# Vale_Project_02.net
KiCad netlist of a schematic drawn in EAGLE
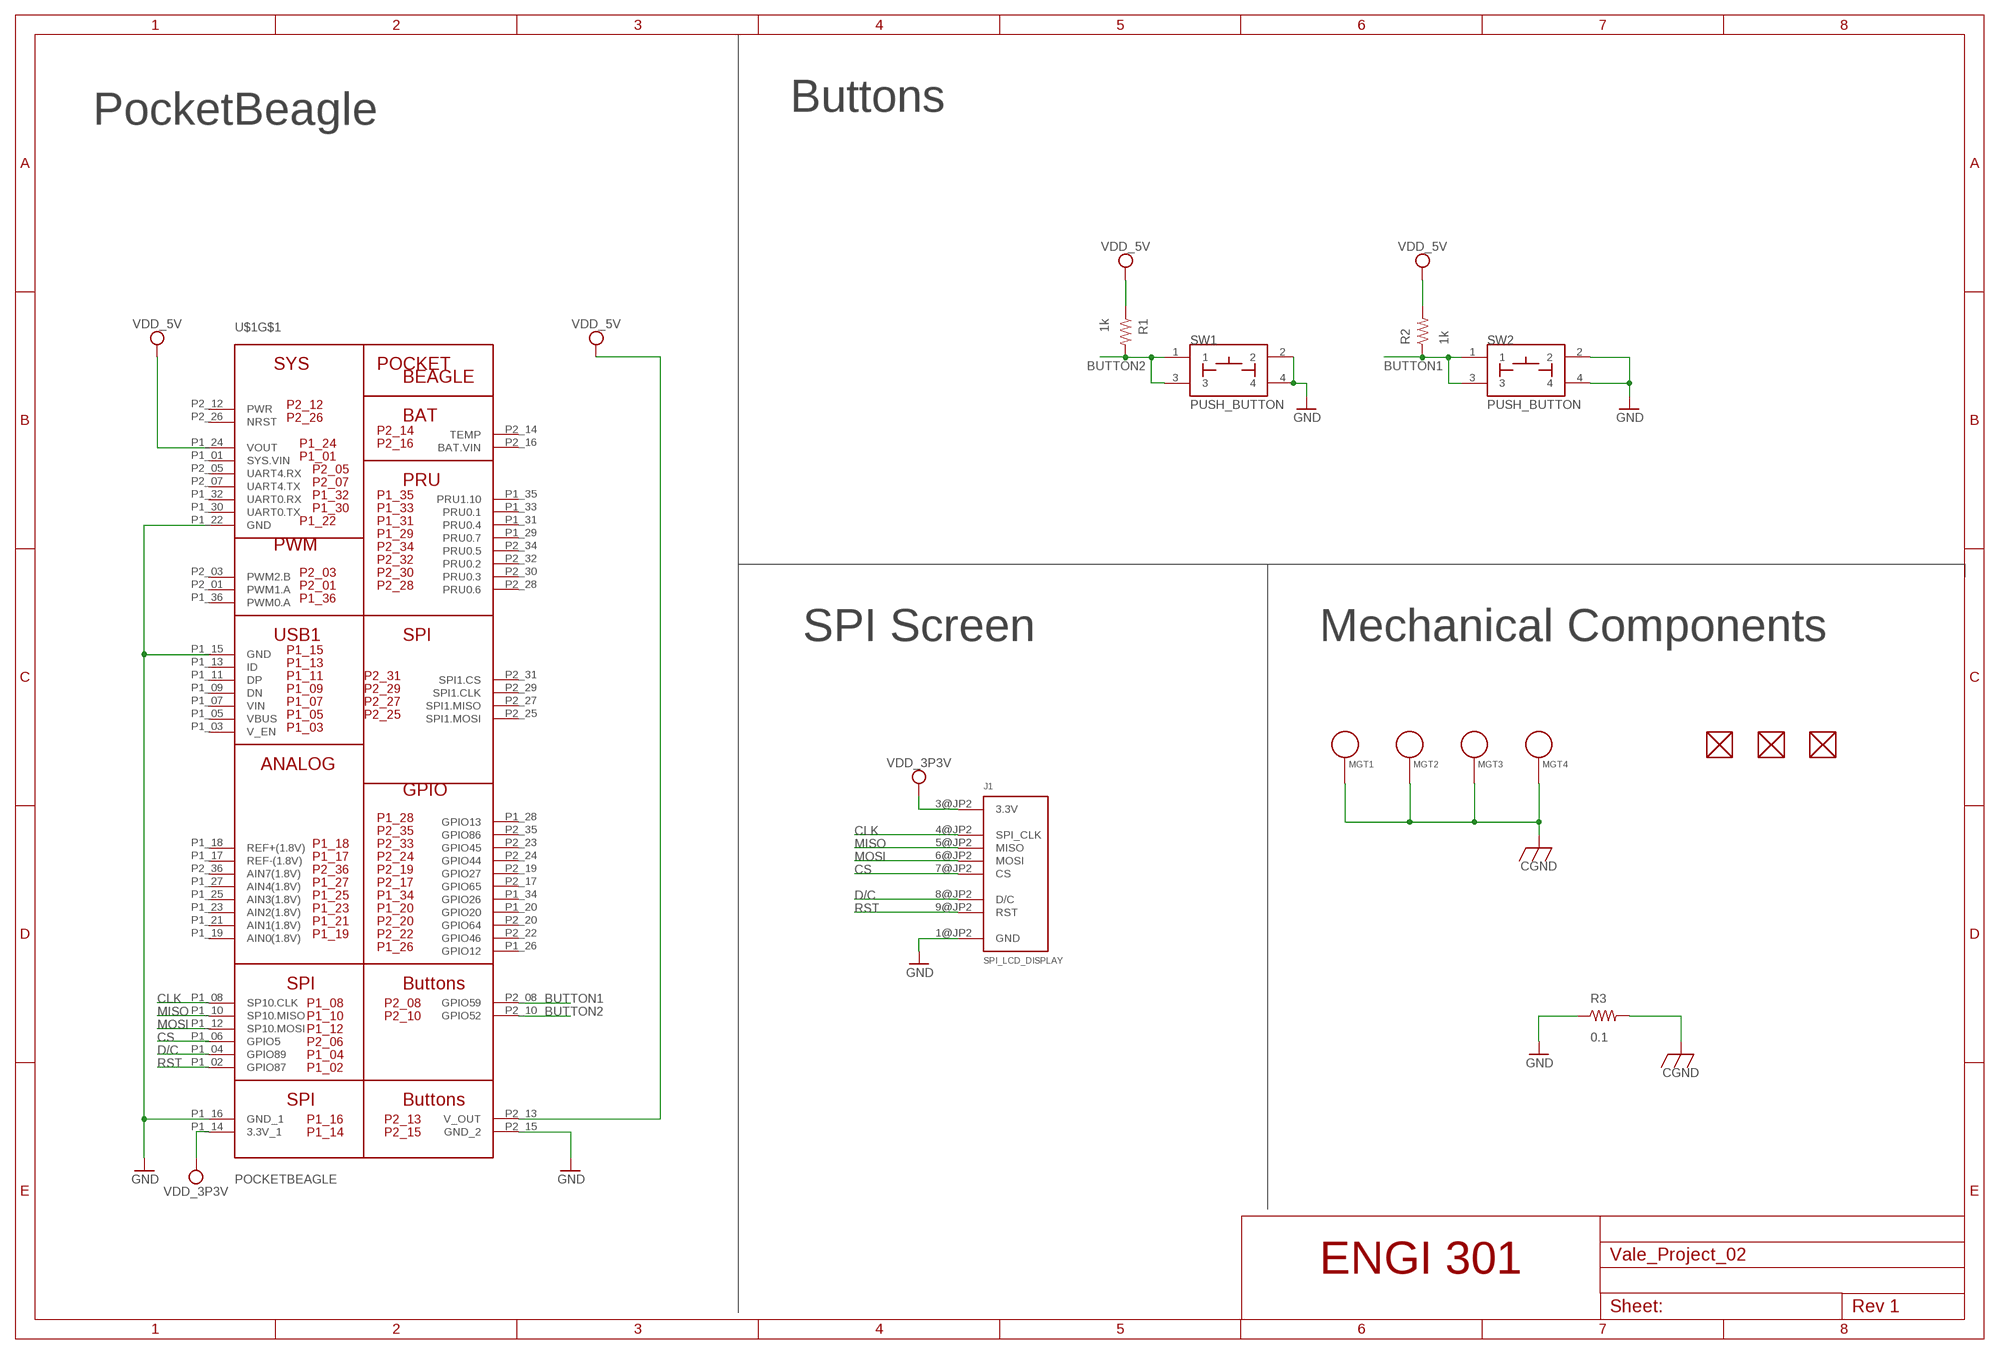
[diagram p0: schematic, sheet 1]

(export (version "E")
  (design (tool "Eeschema 10.0.6"))
  (components
    (comp (ref "FUD1")
      (value "FIDUCIAL")
      (footprint "eagle-import:FIDUCIAL_40MIL")
      (libsource (lib "eagle-import") (part "FIDUCIAL"))
    )
    (comp (ref "FUD2")
      (value "FIDUCIAL")
      (footprint "eagle-import:FIDUCIAL_40MIL")
      (libsource (lib "eagle-import") (part "FIDUCIAL"))
    )
    (comp (ref "FUD3")
      (value "FIDUCIAL")
      (footprint "eagle-import:FIDUCIAL_40MIL")
      (libsource (lib "eagle-import") (part "FIDUCIAL"))
    )
    (comp (ref "J1")
      (value "SPI_LCD_DISPLAY")
      (footprint "eagle-import:SPI_LCD_DISPLAY")
      (libsource (lib "eagle-import") (part "SPI_LCD_DISPLAY"))
    )
    (comp (ref "MGT1")
      (value "MOUNTING_HOLE")
      (footprint "eagle-import:MOUNTING_HOLE")
      (libsource (lib "eagle-import") (part "MOUNTING_HOLE"))
    )
    (comp (ref "MGT2")
      (value "MOUNTING_HOLE")
      (footprint "eagle-import:MOUNTING_HOLE")
      (libsource (lib "eagle-import") (part "MOUNTING_HOLE"))
    )
    (comp (ref "MGT3")
      (value "MOUNTING_HOLE")
      (footprint "eagle-import:MOUNTING_HOLE")
      (libsource (lib "eagle-import") (part "MOUNTING_HOLE"))
    )
    (comp (ref "MGT4")
      (value "MOUNTING_HOLE")
      (footprint "eagle-import:MOUNTING_HOLE")
      (libsource (lib "eagle-import") (part "MOUNTING_HOLE"))
    )
    (comp (ref "R1")
      (value "1k")
      (footprint "eagle-import:R1206")
      (libsource (lib "eagle-import") (part "R_R1206"))
    )
    (comp (ref "R2")
      (value "1k")
      (footprint "eagle-import:R1206")
      (libsource (lib "eagle-import") (part "R_R1206"))
    )
    (comp (ref "R3")
      (value "0.1")
      (footprint "eagle-import:R0805")
      (libsource (lib "eagle-import") (part "R_R0805"))
    )
    (comp (ref "SW1")
      (value "PUSH_BUTTON")
      (footprint "eagle-import:BUTTON_12.5MM")
      (libsource (lib "eagle-import") (part "PUSH_BUTTON"))
    )
    (comp (ref "SW2")
      (value "PUSH_BUTTON")
      (footprint "eagle-import:BUTTON_12.5MM")
      (libsource (lib "eagle-import") (part "PUSH_BUTTON"))
    )
    (comp (ref "U$1")
      (value "POCKETBEAGLE")
      (footprint "eagle-import:POCKETBEAGLE")
      (libsource (lib "eagle-import") (part "POCKETBEAGLE"))
    )
  )
  (nets
    (net (code "1") (name "/BUTTON1") (class "Default")
      (node (ref "R2") (pin "1") (pinfunction "1_1") (pintype "passive"))
      (node (ref "SW2") (pin "1") (pinfunction "1_1") (pintype "bidirectional"))
      (node (ref "SW2") (pin "3") (pinfunction "3_3") (pintype "bidirectional"))
      (node (ref "U$1") (pin "P2_08") (pinfunction "GPIO59_P2_08") (pintype "bidirectional"))
    )
    (net (code "2") (name "/BUTTON2") (class "Default")
      (node (ref "R1") (pin "2") (pinfunction "2_2") (pintype "passive"))
      (node (ref "SW1") (pin "1") (pinfunction "1_1") (pintype "bidirectional"))
      (node (ref "SW1") (pin "3") (pinfunction "3_3") (pintype "bidirectional"))
      (node (ref "U$1") (pin "P2_10") (pinfunction "GPIO52_P2_10") (pintype "bidirectional"))
    )
    (net (code "3") (name "/CLK") (class "Default")
      (node (ref "J1") (pin "4@JP2") (pinfunction "SPI_CLK_4@JP2") (pintype "bidirectional"))
      (node (ref "U$1") (pin "P1_08") (pinfunction "SP10.CLK_P1_08") (pintype "bidirectional"))
    )
    (net (code "4") (name "/CS") (class "Default")
      (node (ref "J1") (pin "7@JP2") (pinfunction "CS_7@JP2") (pintype "bidirectional"))
      (node (ref "U$1") (pin "P1_06") (pinfunction "GPIO5_P1_06") (pintype "bidirectional"))
    )
    (net (code "5") (name "/D{slash}C") (class "Default")
      (node (ref "J1") (pin "8@JP2") (pinfunction "D/C_8@JP2") (pintype "bidirectional"))
      (node (ref "U$1") (pin "P1_04") (pinfunction "GPIO89_P1_04") (pintype "bidirectional"))
    )
    (net (code "6") (name "/MISO") (class "Default")
      (node (ref "J1") (pin "5@JP2") (pinfunction "MISO_5@JP2") (pintype "bidirectional"))
      (node (ref "U$1") (pin "P1_10") (pinfunction "SP10.MISO_P1_10") (pintype "bidirectional"))
    )
    (net (code "7") (name "/MOSI") (class "Default")
      (node (ref "J1") (pin "6@JP2") (pinfunction "MOSI_6@JP2") (pintype "bidirectional"))
      (node (ref "U$1") (pin "P1_12") (pinfunction "SP10.MOSI_P1_12") (pintype "bidirectional"))
    )
    (net (code "8") (name "/RST") (class "Default")
      (node (ref "J1") (pin "9@JP2") (pinfunction "RST_9@JP2") (pintype "bidirectional"))
      (node (ref "U$1") (pin "P1_02") (pinfunction "GPIO87_P1_02") (pintype "bidirectional"))
    )
    (net (code "9") (name "CGND") (class "Default")
      (node (ref "MGT1") (pin "P$1") (pinfunction "P$1_P$1") (pintype "bidirectional"))
      (node (ref "MGT2") (pin "P$1") (pinfunction "P$1_P$1") (pintype "bidirectional"))
      (node (ref "MGT3") (pin "P$1") (pinfunction "P$1_P$1") (pintype "bidirectional"))
      (node (ref "MGT4") (pin "P$1") (pinfunction "P$1_P$1") (pintype "bidirectional"))
      (node (ref "R3") (pin "2") (pinfunction "2_2") (pintype "passive"))
    )
    (net (code "10") (name "GND") (class "Default")
      (node (ref "J1") (pin "1@JP2") (pinfunction "GND_1@JP2") (pintype "bidirectional"))
      (node (ref "R3") (pin "1") (pinfunction "1_1") (pintype "passive"))
      (node (ref "SW1") (pin "2") (pinfunction "2_2") (pintype "bidirectional"))
      (node (ref "SW1") (pin "4") (pinfunction "4_4") (pintype "bidirectional"))
      (node (ref "SW2") (pin "2") (pinfunction "2_2") (pintype "bidirectional"))
      (node (ref "SW2") (pin "4") (pinfunction "4_4") (pintype "bidirectional"))
      (node (ref "U$1") (pin "P1_15") (pinfunction "GND_P1_15") (pintype "bidirectional"))
      (node (ref "U$1") (pin "P1_16") (pinfunction "GND_1_P1_16") (pintype "power_in"))
      (node (ref "U$1") (pin "P1_22") (pinfunction "GND_P1_22") (pintype "bidirectional"))
      (node (ref "U$1") (pin "P2_15") (pinfunction "GND_2_P2_15") (pintype "bidirectional"))
    )
    (net (code "11") (name "VDD_3P3V") (class "Default")
      (node (ref "J1") (pin "3@JP2") (pinfunction "3.3V_3@JP2") (pintype "bidirectional"))
      (node (ref "U$1") (pin "P1_14") (pinfunction "3.3V_1_P1_14") (pintype "power_in"))
    )
    (net (code "12") (name "VDD_5V") (class "Default")
      (node (ref "R1") (pin "1") (pinfunction "1_1") (pintype "passive"))
      (node (ref "R2") (pin "2") (pinfunction "2_2") (pintype "passive"))
      (node (ref "U$1") (pin "P1_24") (pinfunction "VOUT_P1_24") (pintype "bidirectional"))
      (node (ref "U$1") (pin "P2_13") (pinfunction "V_OUT_P2_13") (pintype "bidirectional"))
    )
    (net (code "13") (name "unconnected-(FUD1-PadP$1)") (class "Default")
      (node (ref "FUD1") (pin "P$1") (pinfunction "P$1_P$1") (pintype "no_connect"))
    )
    (net (code "14") (name "unconnected-(FUD2-PadP$1)") (class "Default")
      (node (ref "FUD2") (pin "P$1") (pinfunction "P$1_P$1") (pintype "no_connect"))
    )
    (net (code "15") (name "unconnected-(FUD3-PadP$1)") (class "Default")
      (node (ref "FUD3") (pin "P$1") (pinfunction "P$1_P$1") (pintype "no_connect"))
    )
    (net (code "16") (name "unconnected-(U$1A-AIN0(1.8V)-PadP1_19)") (class "Default")
      (node (ref "U$1") (pin "P1_19") (pinfunction "AIN0(1.8V)_P1_19") (pintype "bidirectional"))
    )
    (net (code "17") (name "unconnected-(U$1A-AIN1(1.8V)-PadP1_21)") (class "Default")
      (node (ref "U$1") (pin "P1_21") (pinfunction "AIN1(1.8V)_P1_21") (pintype "bidirectional"))
    )
    (net (code "18") (name "unconnected-(U$1A-AIN2(1.8V)-PadP1_23)") (class "Default")
      (node (ref "U$1") (pin "P1_23") (pinfunction "AIN2(1.8V)_P1_23") (pintype "bidirectional"))
    )
    (net (code "19") (name "unconnected-(U$1A-AIN3(1.8V)-PadP1_25)") (class "Default")
      (node (ref "U$1") (pin "P1_25") (pinfunction "AIN3(1.8V)_P1_25") (pintype "bidirectional"))
    )
    (net (code "20") (name "unconnected-(U$1A-AIN4(1.8V)-PadP1_27)") (class "Default")
      (node (ref "U$1") (pin "P1_27") (pinfunction "AIN4(1.8V)_P1_27") (pintype "bidirectional"))
    )
    (net (code "21") (name "unconnected-(U$1A-AIN7(1.8V)-PadP2_36)") (class "Default")
      (node (ref "U$1") (pin "P2_36") (pinfunction "AIN7(1.8V)_P2_36") (pintype "bidirectional"))
    )
    (net (code "22") (name "unconnected-(U$1A-BAT.VIN-PadP2_16)") (class "Default")
      (node (ref "U$1") (pin "P2_16") (pinfunction "BAT.VIN_P2_16") (pintype "bidirectional"))
    )
    (net (code "23") (name "unconnected-(U$1A-DN-PadP1_09)") (class "Default")
      (node (ref "U$1") (pin "P1_09") (pinfunction "DN_P1_09") (pintype "bidirectional"))
    )
    (net (code "24") (name "unconnected-(U$1A-DP-PadP1_11)") (class "Default")
      (node (ref "U$1") (pin "P1_11") (pinfunction "DP_P1_11") (pintype "bidirectional"))
    )
    (net (code "25") (name "unconnected-(U$1A-GPIO12-PadP1_26)") (class "Default")
      (node (ref "U$1") (pin "P1_26") (pinfunction "GPIO12_P1_26") (pintype "bidirectional"))
    )
    (net (code "26") (name "unconnected-(U$1A-GPIO13-PadP1_28)") (class "Default")
      (node (ref "U$1") (pin "P1_28") (pinfunction "GPIO13_P1_28") (pintype "bidirectional"))
    )
    (net (code "27") (name "unconnected-(U$1A-GPIO20-PadP1_20)") (class "Default")
      (node (ref "U$1") (pin "P1_20") (pinfunction "GPIO20_P1_20") (pintype "bidirectional"))
    )
    (net (code "28") (name "unconnected-(U$1A-GPIO26-PadP1_34)") (class "Default")
      (node (ref "U$1") (pin "P1_34") (pinfunction "GPIO26_P1_34") (pintype "bidirectional"))
    )
    (net (code "29") (name "unconnected-(U$1A-GPIO27-PadP2_19)") (class "Default")
      (node (ref "U$1") (pin "P2_19") (pinfunction "GPIO27_P2_19") (pintype "bidirectional"))
    )
    (net (code "30") (name "unconnected-(U$1A-GPIO44-PadP2_24)") (class "Default")
      (node (ref "U$1") (pin "P2_24") (pinfunction "GPIO44_P2_24") (pintype "bidirectional"))
    )
    (net (code "31") (name "unconnected-(U$1A-GPIO45-PadP2_23)") (class "Default")
      (node (ref "U$1") (pin "P2_23") (pinfunction "GPIO45_P2_23") (pintype "bidirectional"))
    )
    (net (code "32") (name "unconnected-(U$1A-GPIO46-PadP2_22)") (class "Default")
      (node (ref "U$1") (pin "P2_22") (pinfunction "GPIO46_P2_22") (pintype "bidirectional"))
    )
    (net (code "33") (name "unconnected-(U$1A-GPIO64-PadP2_20)") (class "Default")
      (node (ref "U$1") (pin "P2_20") (pinfunction "GPIO64_P2_20") (pintype "bidirectional"))
    )
    (net (code "34") (name "unconnected-(U$1A-GPIO65-PadP2_17)") (class "Default")
      (node (ref "U$1") (pin "P2_17") (pinfunction "GPIO65_P2_17") (pintype "bidirectional"))
    )
    (net (code "35") (name "unconnected-(U$1A-GPIO86-PadP2_35)") (class "Default")
      (node (ref "U$1") (pin "P2_35") (pinfunction "GPIO86_P2_35") (pintype "bidirectional"))
    )
    (net (code "36") (name "unconnected-(U$1A-ID-PadP1_13)") (class "Default")
      (node (ref "U$1") (pin "P1_13") (pinfunction "ID_P1_13") (pintype "bidirectional"))
    )
    (net (code "37") (name "unconnected-(U$1A-NRST-PadP2_26)") (class "Default")
      (node (ref "U$1") (pin "P2_26") (pinfunction "NRST_P2_26") (pintype "bidirectional"))
    )
    (net (code "38") (name "unconnected-(U$1A-PRU0.1-PadP1_33)") (class "Default")
      (node (ref "U$1") (pin "P1_33") (pinfunction "PRU0.1_P1_33") (pintype "bidirectional"))
    )
    (net (code "39") (name "unconnected-(U$1A-PRU0.2-PadP2_32)") (class "Default")
      (node (ref "U$1") (pin "P2_32") (pinfunction "PRU0.2_P2_32") (pintype "bidirectional"))
    )
    (net (code "40") (name "unconnected-(U$1A-PRU0.3-PadP2_30)") (class "Default")
      (node (ref "U$1") (pin "P2_30") (pinfunction "PRU0.3_P2_30") (pintype "bidirectional"))
    )
    (net (code "41") (name "unconnected-(U$1A-PRU0.4-PadP1_31)") (class "Default")
      (node (ref "U$1") (pin "P1_31") (pinfunction "PRU0.4_P1_31") (pintype "bidirectional"))
    )
    (net (code "42") (name "unconnected-(U$1A-PRU0.5-PadP2_34)") (class "Default")
      (node (ref "U$1") (pin "P2_34") (pinfunction "PRU0.5_P2_34") (pintype "bidirectional"))
    )
    (net (code "43") (name "unconnected-(U$1A-PRU0.6-PadP2_28)") (class "Default")
      (node (ref "U$1") (pin "P2_28") (pinfunction "PRU0.6_P2_28") (pintype "bidirectional"))
    )
    (net (code "44") (name "unconnected-(U$1A-PRU0.7-PadP1_29)") (class "Default")
      (node (ref "U$1") (pin "P1_29") (pinfunction "PRU0.7_P1_29") (pintype "bidirectional"))
    )
    (net (code "45") (name "unconnected-(U$1A-PRU1.10-PadP1_35)") (class "Default")
      (node (ref "U$1") (pin "P1_35") (pinfunction "PRU1.10_P1_35") (pintype "bidirectional"))
    )
    (net (code "46") (name "unconnected-(U$1A-PWM0.A-PadP1_36)") (class "Default")
      (node (ref "U$1") (pin "P1_36") (pinfunction "PWM0.A_P1_36") (pintype "bidirectional"))
    )
    (net (code "47") (name "unconnected-(U$1A-PWM1.A-PadP2_01)") (class "Default")
      (node (ref "U$1") (pin "P2_01") (pinfunction "PWM1.A_P2_01") (pintype "bidirectional"))
    )
    (net (code "48") (name "unconnected-(U$1A-PWM2.B-PadP2_03)") (class "Default")
      (node (ref "U$1") (pin "P2_03") (pinfunction "PWM2.B_P2_03") (pintype "bidirectional"))
    )
    (net (code "49") (name "unconnected-(U$1A-PWR-PadP2_12)") (class "Default")
      (node (ref "U$1") (pin "P2_12") (pinfunction "PWR_P2_12") (pintype "bidirectional"))
    )
    (net (code "50") (name "unconnected-(U$1A-REF+(1.8V)-PadP1_18)") (class "Default")
      (node (ref "U$1") (pin "P1_18") (pinfunction "REF+(1.8V)_P1_18") (pintype "bidirectional"))
    )
    (net (code "51") (name "unconnected-(U$1A-REF-(1.8V)-PadP1_17)") (class "Default")
      (node (ref "U$1") (pin "P1_17") (pinfunction "REF-(1.8V)_P1_17") (pintype "bidirectional"))
    )
    (net (code "52") (name "unconnected-(U$1A-SPI1.CLK-PadP2_29)") (class "Default")
      (node (ref "U$1") (pin "P2_29") (pinfunction "SPI1.CLK_P2_29") (pintype "bidirectional"))
    )
    (net (code "53") (name "unconnected-(U$1A-SPI1.CS-PadP2_31)") (class "Default")
      (node (ref "U$1") (pin "P2_31") (pinfunction "SPI1.CS_P2_31") (pintype "bidirectional"))
    )
    (net (code "54") (name "unconnected-(U$1A-SPI1.MISO-PadP2_27)") (class "Default")
      (node (ref "U$1") (pin "P2_27") (pinfunction "SPI1.MISO_P2_27") (pintype "bidirectional"))
    )
    (net (code "55") (name "unconnected-(U$1A-SPI1.MOSI-PadP2_25)") (class "Default")
      (node (ref "U$1") (pin "P2_25") (pinfunction "SPI1.MOSI_P2_25") (pintype "bidirectional"))
    )
    (net (code "56") (name "unconnected-(U$1A-SYS.VIN-PadP1_01)") (class "Default")
      (node (ref "U$1") (pin "P1_01") (pinfunction "SYS.VIN_P1_01") (pintype "bidirectional"))
    )
    (net (code "57") (name "unconnected-(U$1A-TEMP-PadP2_14)") (class "Default")
      (node (ref "U$1") (pin "P2_14") (pinfunction "TEMP_P2_14") (pintype "bidirectional"))
    )
    (net (code "58") (name "unconnected-(U$1A-UART0.RX-PadP1_32)") (class "Default")
      (node (ref "U$1") (pin "P1_32") (pinfunction "UART0.RX_P1_32") (pintype "bidirectional"))
    )
    (net (code "59") (name "unconnected-(U$1A-UART0.TX-PadP1_30)") (class "Default")
      (node (ref "U$1") (pin "P1_30") (pinfunction "UART0.TX_P1_30") (pintype "bidirectional"))
    )
    (net (code "60") (name "unconnected-(U$1A-UART4.RX-PadP2_05)") (class "Default")
      (node (ref "U$1") (pin "P2_05") (pinfunction "UART4.RX_P2_05") (pintype "bidirectional"))
    )
    (net (code "61") (name "unconnected-(U$1A-UART4.TX-PadP2_07)") (class "Default")
      (node (ref "U$1") (pin "P2_07") (pinfunction "UART4.TX_P2_07") (pintype "bidirectional"))
    )
    (net (code "62") (name "unconnected-(U$1A-VBUS-PadP1_05)") (class "Default")
      (node (ref "U$1") (pin "P1_05") (pinfunction "VBUS_P1_05") (pintype "bidirectional"))
    )
    (net (code "63") (name "unconnected-(U$1A-VIN-PadP1_07)") (class "Default")
      (node (ref "U$1") (pin "P1_07") (pinfunction "VIN_P1_07") (pintype "bidirectional"))
    )
    (net (code "64") (name "unconnected-(U$1A-V_EN-PadP1_03)") (class "Default")
      (node (ref "U$1") (pin "P1_03") (pinfunction "V_EN_P1_03") (pintype "bidirectional"))
    )
  )
)
